# ZeroCrossPower.net
KiCad netlist of a schematic drawn in EAGLE
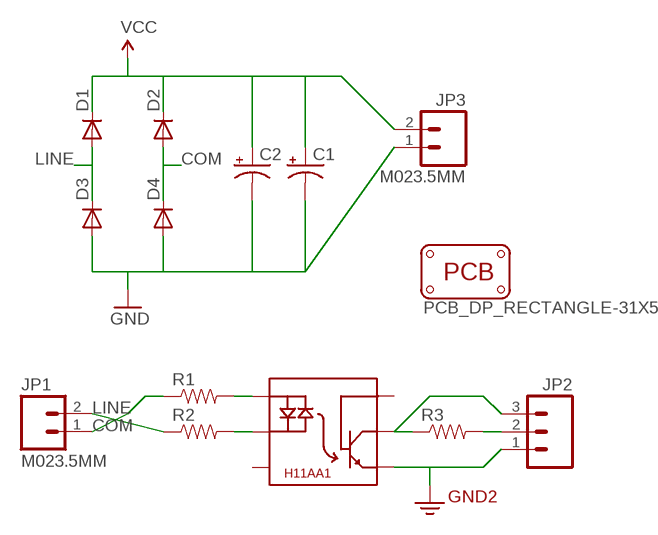
[diagram p0: schematic, sheet 1]

(export (version "E")
  (design (tool "Eeschema 10.0.6"))
  (components
    (comp (ref "C1")
      (value "CAP_POLPTH3")
      (footprint "eagle-import:CPOL-RADIAL-1000UF-63V")
      (libsource (lib "eagle-import") (part "CAP_POLPTH3"))
    )
    (comp (ref "C2")
      (value "CAP_POLPTH4")
      (footprint "eagle-import:CPOL-RADIAL-1000UF-25V")
      (libsource (lib "eagle-import") (part "CAP_POLPTH4"))
    )
    (comp (ref "D1")
      (value "DIODE")
      (footprint "eagle-import:DIODE-1N4001-KIT")
      (libsource (lib "eagle-import") (part "DIODE"))
    )
    (comp (ref "D2")
      (value "DIODE")
      (footprint "eagle-import:DIODE-1N4001-KIT")
      (libsource (lib "eagle-import") (part "DIODE"))
    )
    (comp (ref "D3")
      (value "DIODE")
      (footprint "eagle-import:DIODE-1N4001-KIT")
      (libsource (lib "eagle-import") (part "DIODE"))
    )
    (comp (ref "D4")
      (value "DIODE")
      (footprint "eagle-import:DIODE-1N4001-KIT")
      (libsource (lib "eagle-import") (part "DIODE"))
    )
    (comp (ref "JP1")
      (value "M023.5MM")
      (footprint "eagle-import:SCREWTERMINAL-3.5MM-2")
      (libsource (lib "eagle-import") (part "M023.5MM"))
    )
    (comp (ref "JP2")
      (value "M03PTH")
      (footprint "eagle-import:1X03")
      (libsource (lib "eagle-import") (part "M03PTH"))
    )
    (comp (ref "JP3")
      (value "M023.5MM")
      (footprint "eagle-import:SCREWTERMINAL-3.5MM-2")
      (libsource (lib "eagle-import") (part "M023.5MM"))
    )
    (comp (ref "PCB1")
      (value "PCB_DP_RECTANGLE-31X50")
      (footprint "eagle-import:DP5031_V1")
      (libsource (lib "eagle-import") (part "PCB_DP_RECTANGLE-31X50"))
    )
    (comp (ref "R1")
      (value "RESISTORAXIAL-0.3")
      (footprint "eagle-import:AXIAL-0.3")
      (libsource (lib "eagle-import") (part "RESISTORAXIAL-0.3"))
    )
    (comp (ref "R2")
      (value "RESISTORAXIAL-0.3")
      (footprint "eagle-import:AXIAL-0.3")
      (libsource (lib "eagle-import") (part "RESISTORAXIAL-0.3"))
    )
    (comp (ref "R3")
      (value "RESISTORAXIAL-0.3")
      (footprint "eagle-import:AXIAL-0.3")
      (libsource (lib "eagle-import") (part "RESISTORAXIAL-0.3"))
    )
    (comp (ref "U$1")
      (value "H11AA1")
      (footprint "eagle-import:DIP6")
      (libsource (lib "eagle-import") (part "H11AA1"))
    )
  )
  (nets
    (net (code "1") (name "/COM") (class "Default")
      (node (ref "D2") (pin "A") (pinfunction "A_A") (pintype "passive"))
      (node (ref "D4") (pin "C") (pinfunction "C_C") (pintype "passive"))
      (node (ref "JP1") (pin "2") (pinfunction "2_2") (pintype "passive"))
      (node (ref "R2") (pin "P$1") (pinfunction "1_P$1") (pintype "passive"))
    )
    (net (code "2") (name "/LINE") (class "Default")
      (node (ref "D1") (pin "A") (pinfunction "A_A") (pintype "passive"))
      (node (ref "D3") (pin "C") (pinfunction "C_C") (pintype "passive"))
      (node (ref "JP1") (pin "1") (pinfunction "1_1") (pintype "passive"))
      (node (ref "R1") (pin "P$1") (pinfunction "1_P$1") (pintype "passive"))
    )
    (net (code "3") (name "GND") (class "Default")
      (node (ref "C1") (pin "2") (pinfunction "-_2") (pintype "passive"))
      (node (ref "C2") (pin "2") (pinfunction "-_2") (pintype "passive"))
      (node (ref "D3") (pin "A") (pinfunction "A_A") (pintype "passive"))
      (node (ref "D4") (pin "A") (pinfunction "A_A") (pintype "passive"))
      (node (ref "JP3") (pin "1") (pinfunction "1_1") (pintype "passive"))
    )
    (net (code "4") (name "GND2") (class "Default")
      (node (ref "JP2") (pin "1") (pinfunction "1_1") (pintype "passive"))
      (node (ref "U$1") (pin "4") (pinfunction "E_4") (pintype "bidirectional"))
    )
    (net (code "5") (name "Net-(R1-2)") (class "Default")
      (node (ref "R1") (pin "P$2") (pinfunction "2_P$2") (pintype "passive"))
      (node (ref "U$1") (pin "1") (pinfunction "A/C_1") (pintype "bidirectional"))
    )
    (net (code "6") (name "Net-(R2-2)") (class "Default")
      (node (ref "R2") (pin "P$2") (pinfunction "2_P$2") (pintype "passive"))
      (node (ref "U$1") (pin "2") (pinfunction "C/A_2") (pintype "bidirectional"))
    )
    (net (code "7") (name "Net-(R3-1)") (class "Default")
      (node (ref "JP2") (pin "3") (pinfunction "3_3") (pintype "passive"))
      (node (ref "R3") (pin "P$1") (pinfunction "1_P$1") (pintype "passive"))
      (node (ref "U$1") (pin "5") (pinfunction "C_5") (pintype "bidirectional"))
    )
    (net (code "8") (name "Net-(R3-2)") (class "Default")
      (node (ref "JP2") (pin "2") (pinfunction "2_2") (pintype "passive"))
      (node (ref "R3") (pin "P$2") (pinfunction "2_P$2") (pintype "passive"))
    )
    (net (code "9") (name "VCC") (class "Default")
      (node (ref "C1") (pin "1") (pinfunction "+_1") (pintype "passive"))
      (node (ref "C2") (pin "1") (pinfunction "+_1") (pintype "passive"))
      (node (ref "D1") (pin "C") (pinfunction "C_C") (pintype "passive"))
      (node (ref "D2") (pin "C") (pinfunction "C_C") (pintype "passive"))
      (node (ref "JP3") (pin "2") (pinfunction "2_2") (pintype "passive"))
    )
    (net (code "10") (name "unconnected-(U$1-B-Pad6)") (class "Default")
      (node (ref "U$1") (pin "6") (pinfunction "B_6") (pintype "bidirectional"))
    )
    (net (code "11") (name "unconnected-(U$1-NC-Pad3)") (class "Default")
      (node (ref "U$1") (pin "3") (pinfunction "NC_3") (pintype "bidirectional"))
    )
  )
)
